# CO2_Shield.net
KiCad netlist of a schematic drawn in EAGLE
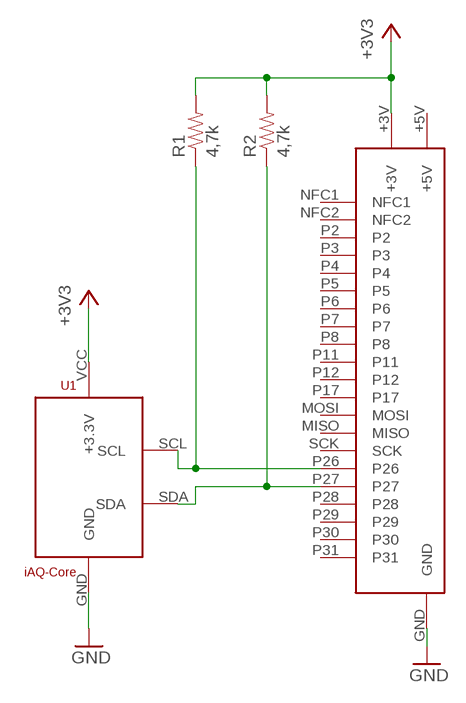
[diagram p0: schematic, sheet 1]

(export (version "E")
  (design (tool "Eeschema 10.0.6"))
  (components
    (comp (ref "R1")
      (value "4,7k")
      (footprint "eagle-import:0805")
      (libsource (lib "eagle-import") (part "510OHM1/4W1%(0805)"))
    )
    (comp (ref "R2")
      (value "4,7k")
      (footprint "eagle-import:0805")
      (libsource (lib "eagle-import") (part "510OHM1/4W1%(0805)"))
    )
    (comp (ref "U$1")
      (value "EE02_SHIELD_HEADERSHIELD")
      (footprint "eagle-import:EE02_SHIELD_HEADER")
      (libsource (lib "eagle-import") (part "EE02_SHIELD_HEADERSHIELD"))
    )
    (comp (ref "U1")
      (value "iAQ-Core")
      (footprint "eagle-import:IAQ-CORE")
      (libsource (lib "eagle-import") (part "IAQ-CORE"))
    )
  )
  (nets
    (net (code "1") (name "+3V3") (class "Default")
      (node (ref "R1") (pin "2") (pinfunction "2_2") (pintype "passive"))
      (node (ref "R2") (pin "2") (pinfunction "2_2") (pintype "passive"))
      (node (ref "U$1") (pin "+3V") (pinfunction "+3V_+3V") (pintype "bidirectional"))
      (node (ref "U1") (pin "VCC") (pinfunction "+3.3V_VCC") (pintype "bidirectional"))
    )
    (net (code "2") (name "GND") (class "Default")
      (node (ref "U$1") (pin "GND") (pinfunction "GND_GND") (pintype "bidirectional"))
      (node (ref "U1") (pin "GND") (pinfunction "GND_GND") (pintype "bidirectional"))
    )
    (net (code "3") (name "Net-(R1-Pad1)") (class "Default")
      (node (ref "R1") (pin "1") (pinfunction "1_1") (pintype "passive"))
      (node (ref "U$1") (pin "P26") (pinfunction "P26_P26") (pintype "bidirectional"))
      (node (ref "U1") (pin "SCL") (pinfunction "SCL_SCL") (pintype "bidirectional"))
    )
    (net (code "4") (name "Net-(R2-Pad1)") (class "Default")
      (node (ref "R2") (pin "1") (pinfunction "1_1") (pintype "passive"))
      (node (ref "U$1") (pin "P27") (pinfunction "P27_P27") (pintype "bidirectional"))
      (node (ref "U1") (pin "SDA") (pinfunction "SDA_SDA") (pintype "bidirectional"))
    )
    (net (code "5") (name "unconnected-(U$1-Pad+5V)") (class "Default")
      (node (ref "U$1") (pin "+5V") (pinfunction "+5V_+5V") (pintype "bidirectional"))
    )
    (net (code "6") (name "unconnected-(U$1-PadMISO)") (class "Default")
      (node (ref "U$1") (pin "MISO") (pinfunction "MISO_MISO") (pintype "bidirectional"))
    )
    (net (code "7") (name "unconnected-(U$1-PadMOSI)") (class "Default")
      (node (ref "U$1") (pin "MOSI") (pinfunction "MOSI_MOSI") (pintype "bidirectional"))
    )
    (net (code "8") (name "unconnected-(U$1-PadNFC1)") (class "Default")
      (node (ref "U$1") (pin "NFC1") (pinfunction "NFC1_NFC1") (pintype "bidirectional"))
    )
    (net (code "9") (name "unconnected-(U$1-PadNFC2)") (class "Default")
      (node (ref "U$1") (pin "NFC2") (pinfunction "NFC2_NFC2") (pintype "bidirectional"))
    )
    (net (code "10") (name "unconnected-(U$1-PadP2)") (class "Default")
      (node (ref "U$1") (pin "P2") (pinfunction "P2_P2") (pintype "bidirectional"))
    )
    (net (code "11") (name "unconnected-(U$1-PadP3)") (class "Default")
      (node (ref "U$1") (pin "P3") (pinfunction "P3_P3") (pintype "bidirectional"))
    )
    (net (code "12") (name "unconnected-(U$1-PadP4)") (class "Default")
      (node (ref "U$1") (pin "P4") (pinfunction "P4_P4") (pintype "bidirectional"))
    )
    (net (code "13") (name "unconnected-(U$1-PadP5)") (class "Default")
      (node (ref "U$1") (pin "P5") (pinfunction "P5_P5") (pintype "bidirectional"))
    )
    (net (code "14") (name "unconnected-(U$1-PadP6)") (class "Default")
      (node (ref "U$1") (pin "P6") (pinfunction "P6_P6") (pintype "bidirectional"))
    )
    (net (code "15") (name "unconnected-(U$1-PadP7)") (class "Default")
      (node (ref "U$1") (pin "P7") (pinfunction "P7_P7") (pintype "bidirectional"))
    )
    (net (code "16") (name "unconnected-(U$1-PadP8)") (class "Default")
      (node (ref "U$1") (pin "P8") (pinfunction "P8_P8") (pintype "bidirectional"))
    )
    (net (code "17") (name "unconnected-(U$1-PadP11)") (class "Default")
      (node (ref "U$1") (pin "P11") (pinfunction "P11_P11") (pintype "bidirectional"))
    )
    (net (code "18") (name "unconnected-(U$1-PadP12)") (class "Default")
      (node (ref "U$1") (pin "P12") (pinfunction "P12_P12") (pintype "bidirectional"))
    )
    (net (code "19") (name "unconnected-(U$1-PadP17)") (class "Default")
      (node (ref "U$1") (pin "P17") (pinfunction "P17_P17") (pintype "bidirectional"))
    )
    (net (code "20") (name "unconnected-(U$1-PadP28)") (class "Default")
      (node (ref "U$1") (pin "P28") (pinfunction "P28_P28") (pintype "bidirectional"))
    )
    (net (code "21") (name "unconnected-(U$1-PadP29)") (class "Default")
      (node (ref "U$1") (pin "P29") (pinfunction "P29_P29") (pintype "bidirectional"))
    )
    (net (code "22") (name "unconnected-(U$1-PadP30)") (class "Default")
      (node (ref "U$1") (pin "P30") (pinfunction "P30_P30") (pintype "bidirectional"))
    )
    (net (code "23") (name "unconnected-(U$1-PadP31)") (class "Default")
      (node (ref "U$1") (pin "P31") (pinfunction "P31_P31") (pintype "bidirectional"))
    )
    (net (code "24") (name "unconnected-(U$1-PadSCK)") (class "Default")
      (node (ref "U$1") (pin "SCK") (pinfunction "SCK_SCK") (pintype "bidirectional"))
    )
  )
)
